# Chrono_dot.net
KiCad netlist of a schematic drawn in Altium Designer
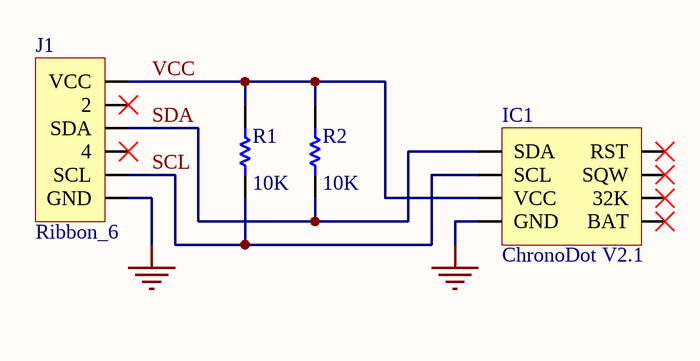
[diagram p0: Chrono_dot.SchDoc]

(export (version "E")
  (design (tool "Eeschema 10.0.6"))
  (components
    (comp (ref "IC1")
      (value "ChronoDot V2.1")
      (footprint "ChronoDot")
      (description "CHRONODOT - ULTRA-PRECISE RTC")
      (libsource (lib "Chrono_dot") (part "ChronoDot V2.1"))
    )
    (comp (ref "J1")
      (value "Ribbon_6")
      (footprint "Ribbon62")
      (description "CONN DIP HDR IDC 6POS VERT")
      (libsource (lib "Chrono_dot") (part "Ribbon_6"))
    )
    (comp (ref "R1")
      (value "10K")
      (footprint "0603")
      (description "Resistor")
      (fields (field (name "Comment") "Res1") (field (name "PUBLISHER") "Altium Limited"))
      (libsource (lib "Miscellaneous Devices") (part "Res1"))
    )
    (comp (ref "R2")
      (value "10K")
      (footprint "0603")
      (description "Resistor")
      (fields (field (name "Comment") "Res1") (field (name "PUBLISHER") "Altium Limited"))
      (libsource (lib "Miscellaneous Devices") (part "Res1"))
    )
  )
  (nets
    (net (code "1") (name "/SCL") (class "Default")
      (node (ref "IC1") (pin "3") (pinfunction "SCL_3") (pintype "passive"))
      (node (ref "J1") (pin "5") (pinfunction "SCL_5") (pintype "passive"))
      (node (ref "R1") (pin "1") (pinfunction "1_1") (pintype "passive"))
    )
    (net (code "2") (name "/SDA") (class "Default")
      (node (ref "IC1") (pin "4") (pinfunction "SDA_4") (pintype "passive"))
      (node (ref "J1") (pin "3") (pinfunction "SDA_3") (pintype "passive"))
      (node (ref "R2") (pin "1") (pinfunction "1_1") (pintype "passive"))
    )
    (net (code "3") (name "/VCC") (class "Default")
      (node (ref "IC1") (pin "2") (pinfunction "VCC_2") (pintype "passive"))
      (node (ref "J1") (pin "1") (pinfunction "VCC_1") (pintype "passive"))
      (node (ref "R1") (pin "2") (pinfunction "2_2") (pintype "passive"))
      (node (ref "R2") (pin "2") (pinfunction "2_2") (pintype "passive"))
    )
    (net (code "4") (name "GND") (class "Default")
      (node (ref "IC1") (pin "1") (pinfunction "GND_1") (pintype "passive"))
      (node (ref "J1") (pin "6") (pinfunction "GND_6") (pintype "passive"))
    )
    (net (code "5") (name "unconnected-(IC1-32K-Pad6)") (class "Default")
      (node (ref "IC1") (pin "6") (pinfunction "32K_6") (pintype "passive+no_connect"))
    )
    (net (code "6") (name "unconnected-(IC1-BAT-Pad5)") (class "Default")
      (node (ref "IC1") (pin "5") (pinfunction "BAT_5") (pintype "passive+no_connect"))
    )
    (net (code "7") (name "unconnected-(IC1-RST-Pad8)") (class "Default")
      (node (ref "IC1") (pin "8") (pinfunction "RST_8") (pintype "passive+no_connect"))
    )
    (net (code "8") (name "unconnected-(IC1-SQW-Pad7)") (class "Default")
      (node (ref "IC1") (pin "7") (pinfunction "SQW_7") (pintype "passive+no_connect"))
    )
    (net (code "9") (name "unconnected-(J1-Pad2)") (class "Default")
      (node (ref "J1") (pin "2") (pinfunction "2_2") (pintype "passive+no_connect"))
    )
    (net (code "10") (name "unconnected-(J1-Pad4)") (class "Default")
      (node (ref "J1") (pin "4") (pinfunction "4_4") (pintype "passive+no_connect"))
    )
  )
)
